# design.net
KiCad netlist of a schematic drawn in Altium Designer
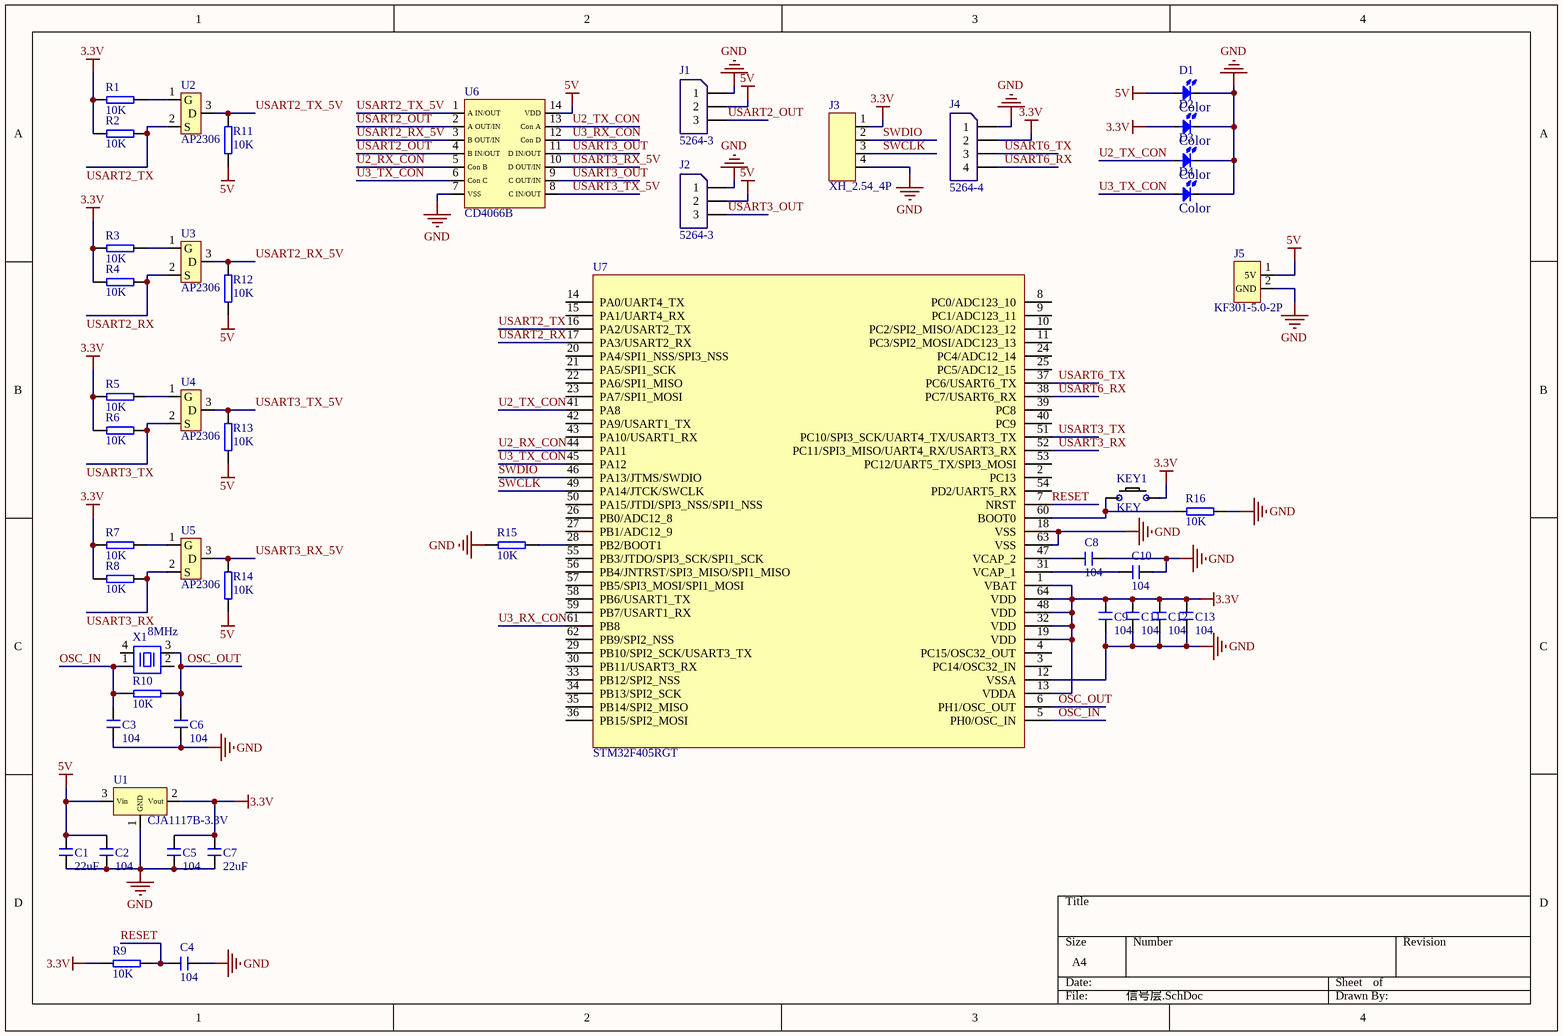
[diagram p0: 信号层.SchDoc]

(export (version "E")
  (design (tool "Eeschema 10.0.6"))
  (components
    (comp (ref "C1") (value "22uF") (footprint "1206C") (libsource (lib "信号层") (part "CAP_1206")))
    (comp (ref "C2") (value "104") (footprint "0603C") (libsource (lib "信号层") (part "CAP_0603")))
    (comp (ref "C3") (value "104") (footprint "0603C") (libsource (lib "信号层") (part "CAP_0603")))
    (comp (ref "C4") (value "104") (footprint "0603C") (libsource (lib "信号层") (part "CAP_0603")))
    (comp (ref "C5") (value "104") (footprint "0603C") (libsource (lib "信号层") (part "CAP_0603")))
    (comp (ref "C6") (value "104") (footprint "0603C") (libsource (lib "信号层") (part "CAP_0603")))
    (comp (ref "C7") (value "22uF") (footprint "1206C") (libsource (lib "信号层") (part "CAP_1206")))
    (comp (ref "C8") (value "104") (footprint "0603C") (libsource (lib "信号层") (part "CAP_0603")))
    (comp (ref "C9") (value "104") (footprint "0603C") (libsource (lib "信号层") (part "CAP_0603")))
    (comp (ref "C10") (value "104") (footprint "0603C") (libsource (lib "信号层") (part "CAP_0603")))
    (comp (ref "C11") (value "104") (footprint "0603C") (libsource (lib "信号层") (part "CAP_0603")))
    (comp (ref "C12") (value "104") (footprint "0603C") (libsource (lib "信号层") (part "CAP_0603")))
    (comp (ref "C13") (value "104") (footprint "0603C") (libsource (lib "信号层") (part "CAP_0603")))
    (comp (ref "D1")
      (value "Color")
      (footprint "0603Led")
      (fields (field (name "Comment") "LED0603"))
      (libsource (lib "信号层") (part "LED0603"))
    )
    (comp (ref "D2")
      (value "Color")
      (footprint "0603Led")
      (fields (field (name "Comment") "LED0603"))
      (libsource (lib "信号层") (part "LED0603"))
    )
    (comp (ref "D3")
      (value "Color")
      (footprint "0603Led")
      (fields (field (name "Comment") "LED0603"))
      (libsource (lib "信号层") (part "LED0603"))
    )
    (comp (ref "D4")
      (value "Color")
      (footprint "0603Led")
      (fields (field (name "Comment") "LED0603"))
      (libsource (lib "信号层") (part "LED0603"))
    )
    (comp (ref "J1")
      (value "5264-3")
      (footprint "5264-3")
      (description "电机连接线")
      (libsource (lib "信号层") (part "5264-3"))
    )
    (comp (ref "J2")
      (value "5264-3")
      (footprint "5264-3")
      (description "电机连接线")
      (libsource (lib "信号层") (part "5264-3"))
    )
    (comp (ref "J3")
      (value "XH_2.54_4P")
      (footprint "XH-2.54_7P_2.54")
      (description "端子")
      (libsource (lib "信号层") (part "XH_2.54_4P"))
    )
    (comp (ref "J4")
      (value "5264-4")
      (footprint "5264-4")
      (description "串口线")
      (libsource (lib "信号层") (part "5264-4"))
    )
    (comp (ref "J5")
      (value "KF301-5.0-2P")
      (footprint "KF301-2P-DC")
      (description "电源输入")
      (libsource (lib "信号层") (part "KF301-5.0-2P"))
    )
    (comp (ref "KEY1")
      (value "KEY")
      (footprint "KEY-SMD_2P-L6.0-W6.0-P6.00")
      (libsource (lib "信号层") (part "KEY"))
    )
    (comp (ref "R1") (value "10K") (footprint "0603R") (libsource (lib "信号层") (part "RES")))
    (comp (ref "R2") (value "10K") (footprint "0603R") (libsource (lib "信号层") (part "RES")))
    (comp (ref "R3") (value "10K") (footprint "0603R") (libsource (lib "信号层") (part "RES")))
    (comp (ref "R4") (value "10K") (footprint "0603R") (libsource (lib "信号层") (part "RES")))
    (comp (ref "R5") (value "10K") (footprint "0603R") (libsource (lib "信号层") (part "RES")))
    (comp (ref "R6") (value "10K") (footprint "0603R") (libsource (lib "信号层") (part "RES")))
    (comp (ref "R7") (value "10K") (footprint "0603R") (libsource (lib "信号层") (part "RES")))
    (comp (ref "R8") (value "10K") (footprint "0603R") (libsource (lib "信号层") (part "RES")))
    (comp (ref "R9") (value "10K") (footprint "0603R") (libsource (lib "信号层") (part "RES")))
    (comp (ref "R10") (value "10K") (footprint "0603R") (libsource (lib "信号层") (part "RES")))
    (comp (ref "R11") (value "10K") (footprint "0603R") (libsource (lib "信号层") (part "RES")))
    (comp (ref "R12") (value "10K") (footprint "0603R") (libsource (lib "信号层") (part "RES")))
    (comp (ref "R13") (value "10K") (footprint "0603R") (libsource (lib "信号层") (part "RES")))
    (comp (ref "R14") (value "10K") (footprint "0603R") (libsource (lib "信号层") (part "RES")))
    (comp (ref "R15") (value "10K") (footprint "0603R") (libsource (lib "信号层") (part "RES")))
    (comp (ref "R16") (value "10K") (footprint "0603R") (libsource (lib "信号层") (part "RES")))
    (comp (ref "U1")
      (value "CJA1117B-3.3V")
      (footprint "SOT-89-3_L4.5-W2.5-P1.50-LS4.2-BR")
      (description "STM32电源输入")
      (libsource (lib "信号层") (part "CJA1117B-3.3V"))
    )
    (comp (ref "U2")
      (value "AP2306")
      (footprint "SOT-23-3_L2.9-W1.6-P1.90-LS2.8-BR")
      (description "NMOS")
      (libsource (lib "信号层") (part "AP2306"))
    )
    (comp (ref "U3")
      (value "AP2306")
      (footprint "SOT-23-3_L2.9-W1.6-P1.90-LS2.8-BR")
      (description "NMOS")
      (libsource (lib "信号层") (part "AP2306"))
    )
    (comp (ref "U4")
      (value "AP2306")
      (footprint "SOT-23-3_L2.9-W1.6-P1.90-LS2.8-BR")
      (description "NMOS")
      (libsource (lib "信号层") (part "AP2306"))
    )
    (comp (ref "U5")
      (value "AP2306")
      (footprint "SOT-23-3_L2.9-W1.6-P1.90-LS2.8-BR")
      (description "NMOS")
      (libsource (lib "信号层") (part "AP2306"))
    )
    (comp (ref "U6")
      (value "CD4066B")
      (footprint "TSSOP-14_L5.0-W4.4-P0.65-LS6.4-BL")
      (description "双向传输门（FET开关）")
      (libsource (lib "信号层") (part "CD4066B"))
    )
    (comp (ref "U7")
      (value "STM32F405RGT")
      (footprint "LQFP64")
      (libsource (lib "信号层") (part "STM32F405RGT"))
    )
    (comp (ref "X1")
      (value "8MHz")
      (footprint "CRYSTAL-SMD_4P-L5.0-W3.2-BL")
      (description "无源晶体")
      (libsource (lib "信号层") (part "X1H008000DK1H-X"))
    )
  )
  (nets
    (net (code "1") (name "/OSC_IN") (class "Default")
      (node (ref "C3") (pin "2") (pinfunction "2_2") (pintype "passive"))
      (node (ref "R10") (pin "1") (pinfunction "1_1") (pintype "passive"))
      (node (ref "U7") (pin "5") (pinfunction "PH0/OSC_IN_5") (pintype "passive"))
      (node (ref "X1") (pin "1") (pinfunction "1_1") (pintype "passive"))
    )
    (net (code "2") (name "/OSC_OUT") (class "Default")
      (node (ref "C6") (pin "2") (pinfunction "2_2") (pintype "passive"))
      (node (ref "R10") (pin "2") (pinfunction "2_2") (pintype "passive"))
      (node (ref "U7") (pin "6") (pinfunction "PH1/OSC_OUT_6") (pintype "passive"))
      (node (ref "X1") (pin "3") (pinfunction "3_3") (pintype "passive"))
    )
    (net (code "3") (name "/RESET") (class "Default")
      (node (ref "C4") (pin "1") (pinfunction "1_1") (pintype "passive"))
      (node (ref "R9") (pin "2") (pinfunction "2_2") (pintype "passive"))
      (node (ref "U7") (pin "7") (pinfunction "NRST_7") (pintype "passive"))
    )
    (net (code "4") (name "/SWCLK") (class "Default")
      (node (ref "J3") (pin "3") (pinfunction "3_3") (pintype "passive"))
      (node (ref "U7") (pin "49") (pinfunction "PA14/JTCK/SWCLK_49") (pintype "passive"))
    )
    (net (code "5") (name "/SWDIO") (class "Default")
      (node (ref "J3") (pin "2") (pinfunction "2_2") (pintype "passive"))
      (node (ref "U7") (pin "46") (pinfunction "PA13/JTMS/SWDIO_46") (pintype "passive"))
    )
    (net (code "6") (name "/U2_RX_CON") (class "Default")
      (node (ref "U6") (pin "5") (pinfunction "Con_B_5") (pintype "passive"))
      (node (ref "U7") (pin "44") (pinfunction "PA11_44") (pintype "passive"))
    )
    (net (code "7") (name "/U2_TX_CON") (class "Default")
      (node (ref "D3") (pin "2") (pinfunction "2_2") (pintype "passive"))
      (node (ref "U6") (pin "13") (pinfunction "Con_A_13") (pintype "passive"))
      (node (ref "U7") (pin "41") (pinfunction "PA8_41") (pintype "passive"))
    )
    (net (code "8") (name "/U3_RX_CON") (class "Default")
      (node (ref "U6") (pin "12") (pinfunction "Con_D_12") (pintype "passive"))
      (node (ref "U7") (pin "61") (pinfunction "PB8_61") (pintype "passive"))
    )
    (net (code "9") (name "/U3_TX_CON") (class "Default")
      (node (ref "D4") (pin "2") (pinfunction "2_2") (pintype "passive"))
      (node (ref "U6") (pin "6") (pinfunction "Con_C_6") (pintype "passive"))
      (node (ref "U7") (pin "45") (pinfunction "PA12_45") (pintype "passive"))
    )
    (net (code "10") (name "/USART2_OUT") (class "Default")
      (node (ref "J1") (pin "3") (pinfunction "3_3") (pintype "passive"))
      (node (ref "U6") (pin "2") (pinfunction "A_OUT/IN_2") (pintype "passive"))
      (node (ref "U6") (pin "4") (pinfunction "B_IN/OUT_4") (pintype "passive"))
    )
    (net (code "11") (name "/USART2_RX") (class "Default")
      (node (ref "R4") (pin "2") (pinfunction "2_2") (pintype "passive"))
      (node (ref "U3") (pin "2") (pinfunction "S_2") (pintype "passive"))
      (node (ref "U7") (pin "17") (pinfunction "PA3/USART2_RX_17") (pintype "passive"))
    )
    (net (code "12") (name "/USART2_RX_5V") (class "Default")
      (node (ref "R12") (pin "2") (pinfunction "2_2") (pintype "passive"))
      (node (ref "U3") (pin "3") (pinfunction "D_3") (pintype "passive"))
      (node (ref "U6") (pin "3") (pinfunction "B_OUT/IN_3") (pintype "passive"))
    )
    (net (code "13") (name "/USART2_TX") (class "Default")
      (node (ref "R2") (pin "2") (pinfunction "2_2") (pintype "passive"))
      (node (ref "U2") (pin "2") (pinfunction "S_2") (pintype "passive"))
      (node (ref "U7") (pin "16") (pinfunction "PA2/USART2_TX_16") (pintype "passive"))
    )
    (net (code "14") (name "/USART2_TX_5V") (class "Default")
      (node (ref "R11") (pin "2") (pinfunction "2_2") (pintype "passive"))
      (node (ref "U2") (pin "3") (pinfunction "D_3") (pintype "passive"))
      (node (ref "U6") (pin "1") (pinfunction "A_IN/OUT_1") (pintype "passive"))
    )
    (net (code "15") (name "/USART3_OUT") (class "Default")
      (node (ref "J2") (pin "3") (pinfunction "3_3") (pintype "passive"))
      (node (ref "U6") (pin "11") (pinfunction "D_IN/OUT_11") (pintype "passive"))
      (node (ref "U6") (pin "9") (pinfunction "C_OUT/IN_9") (pintype "passive"))
    )
    (net (code "16") (name "/USART3_RX") (class "Default")
      (node (ref "R8") (pin "2") (pinfunction "2_2") (pintype "passive"))
      (node (ref "U5") (pin "2") (pinfunction "S_2") (pintype "passive"))
      (node (ref "U7") (pin "52") (pinfunction "PC11/SPI3_MISO/UART4_RX/USART3_RX_52") (pintype "passive"))
    )
    (net (code "17") (name "/USART3_RX_5V") (class "Default")
      (node (ref "R14") (pin "2") (pinfunction "2_2") (pintype "passive"))
      (node (ref "U5") (pin "3") (pinfunction "D_3") (pintype "passive"))
      (node (ref "U6") (pin "10") (pinfunction "D_OUT/IN_10") (pintype "passive"))
    )
    (net (code "18") (name "/USART3_TX") (class "Default")
      (node (ref "R6") (pin "2") (pinfunction "2_2") (pintype "passive"))
      (node (ref "U4") (pin "2") (pinfunction "S_2") (pintype "passive"))
      (node (ref "U7") (pin "51") (pinfunction "PC10/SPI3_SCK/UART4_TX/USART3_TX_51") (pintype "passive"))
    )
    (net (code "19") (name "/USART3_TX_5V") (class "Default")
      (node (ref "R13") (pin "2") (pinfunction "2_2") (pintype "passive"))
      (node (ref "U4") (pin "3") (pinfunction "D_3") (pintype "passive"))
      (node (ref "U6") (pin "8") (pinfunction "C_IN/OUT_8") (pintype "passive"))
    )
    (net (code "20") (name "/USART6_RX") (class "Default")
      (node (ref "J4") (pin "4") (pinfunction "4_4") (pintype "passive"))
      (node (ref "U7") (pin "38") (pinfunction "PC7/USART6_RX_38") (pintype "passive"))
    )
    (net (code "21") (name "/USART6_TX") (class "Default")
      (node (ref "J4") (pin "3") (pinfunction "3_3") (pintype "passive"))
      (node (ref "U7") (pin "37") (pinfunction "PC6/USART6_TX_37") (pintype "passive"))
    )
    (net (code "22") (name "3.3V") (class "Default")
      (node (ref "C11") (pin "2") (pinfunction "2_2") (pintype "passive"))
      (node (ref "C12") (pin "2") (pinfunction "2_2") (pintype "passive"))
      (node (ref "C13") (pin "2") (pinfunction "2_2") (pintype "passive"))
      (node (ref "C5") (pin "2") (pinfunction "2_2") (pintype "passive"))
      (node (ref "C7") (pin "2") (pinfunction "2_2") (pintype "passive"))
      (node (ref "C9") (pin "2") (pinfunction "2_2") (pintype "passive"))
      (node (ref "D2") (pin "2") (pinfunction "2_2") (pintype "passive"))
      (node (ref "J3") (pin "1") (pinfunction "1_1") (pintype "passive"))
      (node (ref "J4") (pin "2") (pinfunction "2_2") (pintype "passive"))
      (node (ref "KEY1") (pin "2") (pinfunction "2_2") (pintype "passive"))
      (node (ref "R1") (pin "1") (pinfunction "1_1") (pintype "passive"))
      (node (ref "R2") (pin "1") (pinfunction "1_1") (pintype "passive"))
      (node (ref "R3") (pin "1") (pinfunction "1_1") (pintype "passive"))
      (node (ref "R4") (pin "1") (pinfunction "1_1") (pintype "passive"))
      (node (ref "R5") (pin "1") (pinfunction "1_1") (pintype "passive"))
      (node (ref "R6") (pin "1") (pinfunction "1_1") (pintype "passive"))
      (node (ref "R7") (pin "1") (pinfunction "1_1") (pintype "passive"))
      (node (ref "R8") (pin "1") (pinfunction "1_1") (pintype "passive"))
      (node (ref "R9") (pin "1") (pinfunction "1_1") (pintype "passive"))
      (node (ref "U1") (pin "2") (pinfunction "Vout_2") (pintype "passive"))
      (node (ref "U7") (pin "1") (pinfunction "VBAT_1") (pintype "passive"))
      (node (ref "U7") (pin "13") (pinfunction "VDDA_13") (pintype "passive"))
      (node (ref "U7") (pin "19") (pinfunction "VDD_19") (pintype "passive"))
      (node (ref "U7") (pin "32") (pinfunction "VDD_32") (pintype "passive"))
      (node (ref "U7") (pin "48") (pinfunction "VDD_48") (pintype "passive"))
      (node (ref "U7") (pin "64") (pinfunction "VDD_64") (pintype "passive"))
    )
    (net (code "23") (name "5V") (class "Default")
      (node (ref "C1") (pin "2") (pinfunction "2_2") (pintype "passive"))
      (node (ref "C2") (pin "2") (pinfunction "2_2") (pintype "passive"))
      (node (ref "D1") (pin "2") (pinfunction "2_2") (pintype "passive"))
      (node (ref "J1") (pin "2") (pinfunction "2_2") (pintype "passive"))
      (node (ref "J2") (pin "2") (pinfunction "2_2") (pintype "passive"))
      (node (ref "J5") (pin "1") (pinfunction "5V_1") (pintype "passive"))
      (node (ref "R11") (pin "1") (pinfunction "1_1") (pintype "passive"))
      (node (ref "R12") (pin "1") (pinfunction "1_1") (pintype "passive"))
      (node (ref "R13") (pin "1") (pinfunction "1_1") (pintype "passive"))
      (node (ref "R14") (pin "1") (pinfunction "1_1") (pintype "passive"))
      (node (ref "U1") (pin "3") (pinfunction "Vin_3") (pintype "passive"))
      (node (ref "U6") (pin "14") (pinfunction "VDD_14") (pintype "passive"))
    )
    (net (code "24") (name "GND") (class "Default")
      (node (ref "C1") (pin "1") (pinfunction "1_1") (pintype "passive"))
      (node (ref "C10") (pin "2") (pinfunction "2_2") (pintype "passive"))
      (node (ref "C11") (pin "1") (pinfunction "1_1") (pintype "passive"))
      (node (ref "C12") (pin "1") (pinfunction "1_1") (pintype "passive"))
      (node (ref "C13") (pin "1") (pinfunction "1_1") (pintype "passive"))
      (node (ref "C2") (pin "1") (pinfunction "1_1") (pintype "passive"))
      (node (ref "C3") (pin "1") (pinfunction "1_1") (pintype "passive"))
      (node (ref "C4") (pin "2") (pinfunction "2_2") (pintype "passive"))
      (node (ref "C5") (pin "1") (pinfunction "1_1") (pintype "passive"))
      (node (ref "C6") (pin "1") (pinfunction "1_1") (pintype "passive"))
      (node (ref "C7") (pin "1") (pinfunction "1_1") (pintype "passive"))
      (node (ref "C8") (pin "2") (pinfunction "2_2") (pintype "passive"))
      (node (ref "C9") (pin "1") (pinfunction "1_1") (pintype "passive"))
      (node (ref "D1") (pin "1") (pinfunction "1_1") (pintype "passive"))
      (node (ref "D2") (pin "1") (pinfunction "1_1") (pintype "passive"))
      (node (ref "D3") (pin "1") (pinfunction "1_1") (pintype "passive"))
      (node (ref "D4") (pin "1") (pinfunction "1_1") (pintype "passive"))
      (node (ref "J1") (pin "1") (pinfunction "1_1") (pintype "passive"))
      (node (ref "J2") (pin "1") (pinfunction "1_1") (pintype "passive"))
      (node (ref "J3") (pin "4") (pinfunction "4_4") (pintype "passive"))
      (node (ref "J4") (pin "1") (pinfunction "1_1") (pintype "passive"))
      (node (ref "J5") (pin "2") (pinfunction "GND_2") (pintype "passive"))
      (node (ref "R15") (pin "1") (pinfunction "1_1") (pintype "passive"))
      (node (ref "R16") (pin "1") (pinfunction "1_1") (pintype "passive"))
      (node (ref "U1") (pin "1") (pinfunction "GND_1") (pintype "passive"))
      (node (ref "U6") (pin "7") (pinfunction "VSS_7") (pintype "passive"))
      (node (ref "U7") (pin "12") (pinfunction "VSSA_12") (pintype "passive"))
      (node (ref "U7") (pin "18") (pinfunction "VSS_18") (pintype "passive"))
      (node (ref "U7") (pin "63") (pinfunction "VSS_63") (pintype "passive"))
    )
    (net (code "25") (name "Net-(U2-G)") (class "Default")
      (node (ref "R1") (pin "2") (pinfunction "2_2") (pintype "passive"))
      (node (ref "U2") (pin "1") (pinfunction "G_1") (pintype "passive"))
    )
    (net (code "26") (name "Net-(U3-G)") (class "Default")
      (node (ref "R3") (pin "2") (pinfunction "2_2") (pintype "passive"))
      (node (ref "U3") (pin "1") (pinfunction "G_1") (pintype "passive"))
    )
    (net (code "27") (name "Net-(U4-G)") (class "Default")
      (node (ref "R5") (pin "2") (pinfunction "2_2") (pintype "passive"))
      (node (ref "U4") (pin "1") (pinfunction "G_1") (pintype "passive"))
    )
    (net (code "28") (name "Net-(U5-G)") (class "Default")
      (node (ref "R7") (pin "2") (pinfunction "2_2") (pintype "passive"))
      (node (ref "U5") (pin "1") (pinfunction "G_1") (pintype "passive"))
    )
    (net (code "29") (name "Net-(U7-BOOT0)") (class "Default")
      (node (ref "KEY1") (pin "1") (pinfunction "1_1") (pintype "passive"))
      (node (ref "R16") (pin "2") (pinfunction "2_2") (pintype "passive"))
      (node (ref "U7") (pin "60") (pinfunction "BOOT0_60") (pintype "passive"))
    )
    (net (code "30") (name "Net-(U7-PB2{slash}BOOT1)") (class "Default")
      (node (ref "R15") (pin "2") (pinfunction "2_2") (pintype "passive"))
      (node (ref "U7") (pin "28") (pinfunction "PB2/BOOT1_28") (pintype "passive"))
    )
    (net (code "31") (name "Net-(U7-VCAP_1)") (class "Default")
      (node (ref "C10") (pin "1") (pinfunction "1_1") (pintype "passive"))
      (node (ref "U7") (pin "31") (pinfunction "VCAP_1_31") (pintype "passive"))
    )
    (net (code "32") (name "Net-(U7-VCAP_2)") (class "Default")
      (node (ref "C8") (pin "1") (pinfunction "1_1") (pintype "passive"))
      (node (ref "U7") (pin "47") (pinfunction "VCAP_2_47") (pintype "passive"))
    )
    (net (code "33") (name "unconnected-(U7-PA0{slash}UART4_TX-Pad14)") (class "Default")
      (node (ref "U7") (pin "14") (pinfunction "PA0/UART4_TX_14") (pintype "passive"))
    )
    (net (code "34") (name "unconnected-(U7-PA1{slash}UART4_RX-Pad15)") (class "Default")
      (node (ref "U7") (pin "15") (pinfunction "PA1/UART4_RX_15") (pintype "passive"))
    )
    (net (code "35") (name "unconnected-(U7-PA4{slash}SPI1_NSS{slash}SPI3_NSS-Pad20)") (class "Default")
      (node (ref "U7") (pin "20") (pinfunction "PA4/SPI1_NSS/SPI3_NSS_20") (pintype "passive"))
    )
    (net (code "36") (name "unconnected-(U7-PA5{slash}SPI1_SCK-Pad21)") (class "Default")
      (node (ref "U7") (pin "21") (pinfunction "PA5/SPI1_SCK_21") (pintype "passive"))
    )
    (net (code "37") (name "unconnected-(U7-PA6{slash}SPI1_MISO-Pad22)") (class "Default")
      (node (ref "U7") (pin "22") (pinfunction "PA6/SPI1_MISO_22") (pintype "passive"))
    )
    (net (code "38") (name "unconnected-(U7-PA7{slash}SPI1_MOSI-Pad23)") (class "Default")
      (node (ref "U7") (pin "23") (pinfunction "PA7/SPI1_MOSI_23") (pintype "passive"))
    )
    (net (code "39") (name "unconnected-(U7-PA9{slash}USART1_TX-Pad42)") (class "Default")
      (node (ref "U7") (pin "42") (pinfunction "PA9/USART1_TX_42") (pintype "passive"))
    )
    (net (code "40") (name "unconnected-(U7-PA10{slash}USART1_RX-Pad43)") (class "Default")
      (node (ref "U7") (pin "43") (pinfunction "PA10/USART1_RX_43") (pintype "passive"))
    )
    (net (code "41") (name "unconnected-(U7-PA15{slash}JTDI{slash}SPI3_NSS{slash}SPI1_NSS-Pad50)") (class "Default")
      (node (ref "U7") (pin "50") (pinfunction "PA15/JTDI/SPI3_NSS/SPI1_NSS_50") (pintype "passive"))
    )
    (net (code "42") (name "unconnected-(U7-PB0{slash}ADC12_8-Pad26)") (class "Default")
      (node (ref "U7") (pin "26") (pinfunction "PB0/ADC12_8_26") (pintype "passive"))
    )
    (net (code "43") (name "unconnected-(U7-PB1{slash}ADC12_9-Pad27)") (class "Default")
      (node (ref "U7") (pin "27") (pinfunction "PB1/ADC12_9_27") (pintype "passive"))
    )
    (net (code "44") (name "unconnected-(U7-PB3{slash}JTDO{slash}SPI3_SCK{slash}SPI1_SCK-Pad55)") (class "Default")
      (node (ref "U7") (pin "55") (pinfunction "PB3/JTDO/SPI3_SCK/SPI1_SCK_55") (pintype "passive"))
    )
    (net (code "45") (name "unconnected-(U7-PB4{slash}JNTRST{slash}SPI3_MISO{slash}SPI1_MISO-Pad56)") (class "Default")
      (node (ref "U7") (pin "56") (pinfunction "PB4/JNTRST/SPI3_MISO/SPI1_MISO_56") (pintype "passive"))
    )
    (net (code "46") (name "unconnected-(U7-PB5{slash}SPI3_MOSI{slash}SPI1_MOSI-Pad57)") (class "Default")
      (node (ref "U7") (pin "57") (pinfunction "PB5/SPI3_MOSI/SPI1_MOSI_57") (pintype "passive"))
    )
    (net (code "47") (name "unconnected-(U7-PB6{slash}USART1_TX-Pad58)") (class "Default")
      (node (ref "U7") (pin "58") (pinfunction "PB6/USART1_TX_58") (pintype "passive"))
    )
    (net (code "48") (name "unconnected-(U7-PB7{slash}USART1_RX-Pad59)") (class "Default")
      (node (ref "U7") (pin "59") (pinfunction "PB7/USART1_RX_59") (pintype "passive"))
    )
    (net (code "49") (name "unconnected-(U7-PB9{slash}SPI2_NSS-Pad62)") (class "Default")
      (node (ref "U7") (pin "62") (pinfunction "PB9/SPI2_NSS_62") (pintype "passive"))
    )
    (net (code "50") (name "unconnected-(U7-PB10{slash}SPI2_SCK{slash}USART3_TX-Pad29)") (class "Default")
      (node (ref "U7") (pin "29") (pinfunction "PB10/SPI2_SCK/USART3_TX_29") (pintype "passive"))
    )
    (net (code "51") (name "unconnected-(U7-PB11{slash}USART3_RX-Pad30)") (class "Default")
      (node (ref "U7") (pin "30") (pinfunction "PB11/USART3_RX_30") (pintype "passive"))
    )
    (net (code "52") (name "unconnected-(U7-PB12{slash}SPI2_NSS-Pad33)") (class "Default")
      (node (ref "U7") (pin "33") (pinfunction "PB12/SPI2_NSS_33") (pintype "passive"))
    )
    (net (code "53") (name "unconnected-(U7-PB13{slash}SPI2_SCK-Pad34)") (class "Default")
      (node (ref "U7") (pin "34") (pinfunction "PB13/SPI2_SCK_34") (pintype "passive"))
    )
    (net (code "54") (name "unconnected-(U7-PB14{slash}SPI2_MISO-Pad35)") (class "Default")
      (node (ref "U7") (pin "35") (pinfunction "PB14/SPI2_MISO_35") (pintype "passive"))
    )
    (net (code "55") (name "unconnected-(U7-PB15{slash}SPI2_MOSI-Pad36)") (class "Default")
      (node (ref "U7") (pin "36") (pinfunction "PB15/SPI2_MOSI_36") (pintype "passive"))
    )
    (net (code "56") (name "unconnected-(U7-PC0{slash}ADC123_10-Pad8)") (class "Default")
      (node (ref "U7") (pin "8") (pinfunction "PC0/ADC123_10_8") (pintype "passive"))
    )
    (net (code "57") (name "unconnected-(U7-PC1{slash}ADC123_11-Pad9)") (class "Default")
      (node (ref "U7") (pin "9") (pinfunction "PC1/ADC123_11_9") (pintype "passive"))
    )
    (net (code "58") (name "unconnected-(U7-PC2{slash}SPI2_MISO{slash}ADC123_12-Pad10)") (class "Default")
      (node (ref "U7") (pin "10") (pinfunction "PC2/SPI2_MISO/ADC123_12_10") (pintype "passive"))
    )
    (net (code "59") (name "unconnected-(U7-PC3{slash}SPI2_MOSI{slash}ADC123_13-Pad11)") (class "Default")
      (node (ref "U7") (pin "11") (pinfunction "PC3/SPI2_MOSI/ADC123_13_11") (pintype "passive"))
    )
    (net (code "60") (name "unconnected-(U7-PC4{slash}ADC12_14-Pad24)") (class "Default")
      (node (ref "U7") (pin "24") (pinfunction "PC4/ADC12_14_24") (pintype "passive"))
    )
    (net (code "61") (name "unconnected-(U7-PC5{slash}ADC12_15-Pad25)") (class "Default")
      (node (ref "U7") (pin "25") (pinfunction "PC5/ADC12_15_25") (pintype "passive"))
    )
    (net (code "62") (name "unconnected-(U7-PC8-Pad39)") (class "Default")
      (node (ref "U7") (pin "39") (pinfunction "PC8_39") (pintype "passive"))
    )
    (net (code "63") (name "unconnected-(U7-PC9-Pad40)") (class "Default")
      (node (ref "U7") (pin "40") (pinfunction "PC9_40") (pintype "passive"))
    )
    (net (code "64") (name "unconnected-(U7-PC12{slash}UART5_TX{slash}SPI3_MOSI-Pad53)") (class "Default")
      (node (ref "U7") (pin "53") (pinfunction "PC12/UART5_TX/SPI3_MOSI_53") (pintype "passive"))
    )
    (net (code "65") (name "unconnected-(U7-PC13-Pad2)") (class "Default")
      (node (ref "U7") (pin "2") (pinfunction "PC13_2") (pintype "passive"))
    )
    (net (code "66") (name "unconnected-(U7-PC14{slash}OSC32_IN-Pad3)") (class "Default")
      (node (ref "U7") (pin "3") (pinfunction "PC14/OSC32_IN_3") (pintype "passive"))
    )
    (net (code "67") (name "unconnected-(U7-PC15{slash}OSC32_OUT-Pad4)") (class "Default")
      (node (ref "U7") (pin "4") (pinfunction "PC15/OSC32_OUT_4") (pintype "passive"))
    )
    (net (code "68") (name "unconnected-(U7-PD2{slash}UART5_RX-Pad54)") (class "Default")
      (node (ref "U7") (pin "54") (pinfunction "PD2/UART5_RX_54") (pintype "passive"))
    )
    (net (code "69") (name "unconnected-(X1-Pad2)") (class "Default")
      (node (ref "X1") (pin "2") (pinfunction "2_2") (pintype "passive"))
    )
    (net (code "70") (name "unconnected-(X1-Pad4)") (class "Default")
      (node (ref "X1") (pin "4") (pinfunction "4_4") (pintype "passive"))
    )
  )
)
